# Router40_v2.net
KiCad netlist of a schematic drawn in EAGLE
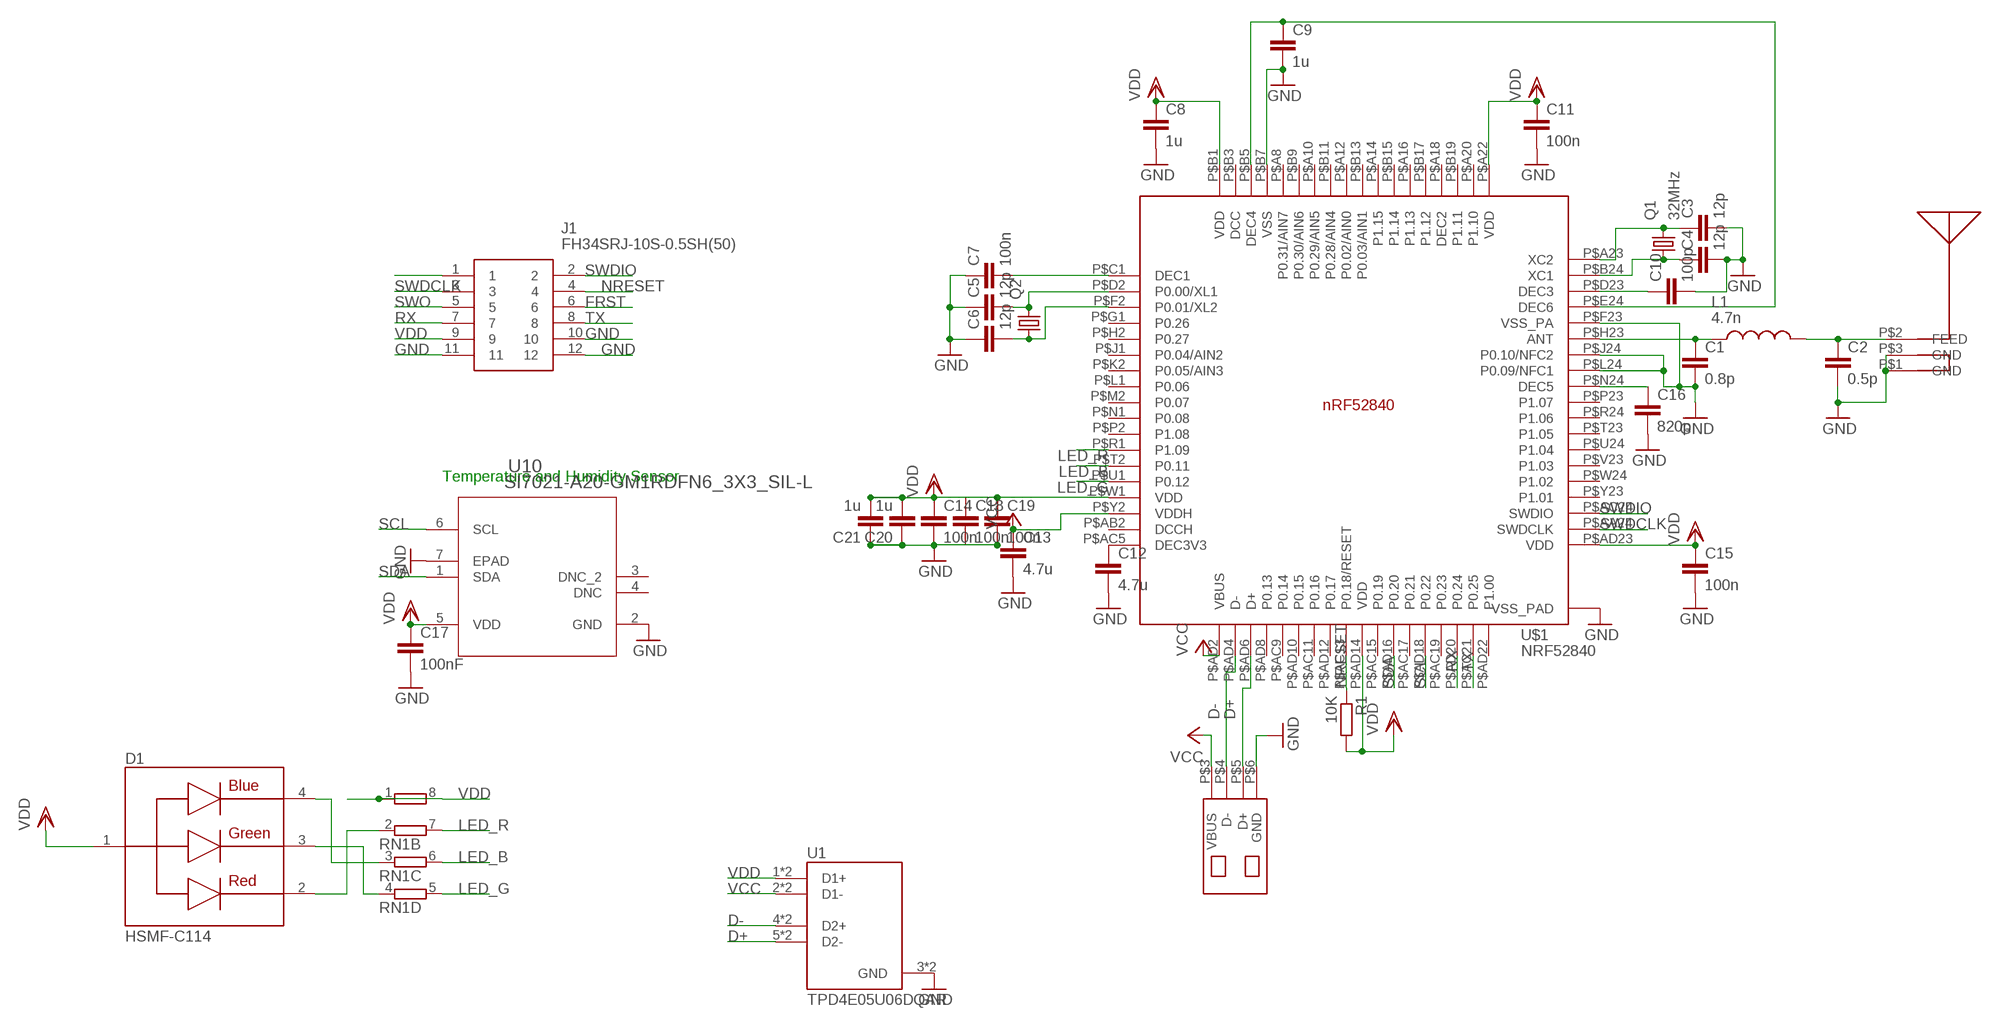
[diagram p0: schematic, sheet 1]

(export (version "E")
  (design (tool "Eeschema 10.0.6"))
  (components
    (comp (ref "C1")
      (value "0.8p")
      (footprint "eagle-import:C0402")
      (libsource (lib "eagle-import") (part "CC0402"))
    )
    (comp (ref "C2")
      (value "0.5p")
      (footprint "eagle-import:C0402")
      (libsource (lib "eagle-import") (part "CC0402"))
    )
    (comp (ref "C3")
      (value "12p")
      (footprint "eagle-import:C0402")
      (libsource (lib "eagle-import") (part "CC0402"))
    )
    (comp (ref "C4")
      (value "12p")
      (footprint "eagle-import:C0402")
      (libsource (lib "eagle-import") (part "CC0402"))
    )
    (comp (ref "C5")
      (value "12p")
      (footprint "eagle-import:C0402")
      (libsource (lib "eagle-import") (part "CC0402"))
    )
    (comp (ref "C6")
      (value "12p")
      (footprint "eagle-import:C0402")
      (libsource (lib "eagle-import") (part "CC0402"))
    )
    (comp (ref "C7")
      (value "100n")
      (footprint "eagle-import:C0402")
      (libsource (lib "eagle-import") (part "CC0402"))
    )
    (comp (ref "C8")
      (value "1u")
      (footprint "eagle-import:C0402")
      (libsource (lib "eagle-import") (part "CC0402"))
    )
    (comp (ref "C9")
      (value "1u")
      (footprint "eagle-import:C0402")
      (libsource (lib "eagle-import") (part "CC0402"))
    )
    (comp (ref "C10")
      (value "100p")
      (footprint "eagle-import:C0402")
      (libsource (lib "eagle-import") (part "CC0402"))
    )
    (comp (ref "C11")
      (value "100n")
      (footprint "eagle-import:C0402")
      (libsource (lib "eagle-import") (part "CC0402"))
    )
    (comp (ref "C12")
      (value "4.7u")
      (footprint "eagle-import:C0402")
      (libsource (lib "eagle-import") (part "CC0402"))
    )
    (comp (ref "C13")
      (value "4.7u")
      (footprint "eagle-import:C0402")
      (libsource (lib "eagle-import") (part "CC0402"))
    )
    (comp (ref "C14")
      (value "100n")
      (footprint "eagle-import:C0402")
      (libsource (lib "eagle-import") (part "CC0402"))
    )
    (comp (ref "C15")
      (value "100n")
      (footprint "eagle-import:C0402")
      (libsource (lib "eagle-import") (part "CC0402"))
    )
    (comp (ref "C16")
      (value "820p")
      (footprint "eagle-import:C0402")
      (libsource (lib "eagle-import") (part "CC0402"))
    )
    (comp (ref "C17")
      (value "100nF")
      (footprint "eagle-import:C0402")
      (libsource (lib "eagle-import") (part "CC0402"))
    )
    (comp (ref "C18")
      (value "100n")
      (footprint "eagle-import:C0402")
      (libsource (lib "eagle-import") (part "CC0402"))
    )
    (comp (ref "C19")
      (value "100n")
      (footprint "eagle-import:C0402")
      (libsource (lib "eagle-import") (part "CC0402"))
    )
    (comp (ref "C20")
      (value "1u")
      (footprint "eagle-import:C0603R")
      (libsource (lib "eagle-import") (part "CC0603R"))
    )
    (comp (ref "C21")
      (value "1u")
      (footprint "eagle-import:C0603R")
      (libsource (lib "eagle-import") (part "CC0603R"))
    )
    (comp (ref "D1")
      (value "HSMF-C114")
      (footprint "eagle-import:DIOSC160X150X35-4N")
      (fields (field (name "MF") "Broadcom Limited"))
      (libsource (lib "eagle-import") (part "HSMF-C114"))
    )
    (comp (ref "J1")
      (value "FH34SRJ-10S-0.5SH(50)")
      (footprint "eagle-import:FH34SRJ10S05SH50")
      (fields (field (name "MF") "Hirose Connector"))
      (libsource (lib "eagle-import") (part "FH34SRJ-10S-0.5SH(50)"))
    )
    (comp (ref "L1")
      (value "4.7n")
      (footprint "eagle-import:INDC0402X26N")
      (fields (field (name "MF") "TDK") (field (name "MP") "MHQ0402P7N5JT000"))
      (libsource (lib "eagle-import") (part "MHQ0402P7N5JT000"))
    )
    (comp (ref "Q1")
      (value "32MHz")
      (footprint "eagle-import:2.0X1.6_KX-5")
      (libsource (lib "eagle-import") (part "KX-5"))
    )
    (comp (ref "Q2")
      (value "KX-327-RT")
      (footprint "eagle-import:2.0X1.2")
      (libsource (lib "eagle-import") (part "KX-327-RT"))
    )
    (comp (ref "R1")
      (value "10K")
      (footprint "eagle-import:R0402")
      (libsource (lib "eagle-import") (part "RR0402"))
    )
    (comp (ref "RN1")
      (value "4R-N0402ARV341")
      (footprint "eagle-import:4X0402ARV341")
      (libsource (lib "eagle-import") (part "4R-N0402ARV341"))
    )
    (comp (ref "U$1")
      (value "NRF52840")
      (footprint "eagle-import:AQFN50P700X700X85_HS-74N")
      (libsource (lib "eagle-import") (part "NRF52840"))
    )
    (comp (ref "U$2")
      (value "USBA_MALE")
      (footprint "eagle-import:USBA_MALE")
      (libsource (lib "eagle-import") (part "USBA_MALE"))
    )
    (comp (ref "U$4")
      (value "CHIPANTENNAL2")
      (footprint "eagle-import:CHIPANTENNAL2")
      (libsource (lib "eagle-import") (part "CHIPANTENNAL2"))
    )
    (comp (ref "U1")
      (value "TPD4E05U06DQAR")
      (footprint "eagle-import:TI_TPD4E05U06DQAR")
      (fields (field (name "MF") "Texas Instruments"))
      (libsource (lib "eagle-import") (part "TPD4E05U06DQAR"))
    )
    (comp (ref "U10")
      (value "SI7021-A20-GM1RDFN6_3X3_SIL-L")
      (footprint "eagle-import:DFN6_3X3_SIL-L")
      (fields
        (field (name "MANUFACTURER_PART_NUMBER") "SI7021-A20-GM1R")
        (field (name "COPYRIGHT") "Copyright (C) 2018 Accelerated Designs. All rights reserved")
      )
      (libsource (lib "eagle-import") (part "SI7021-A20-GM1RDFN6_3X3_SIL-L"))
    )
  )
  (nets
    (net (code "1") (name "/D+") (class "Default")
      (node (ref "U$1") (pin "P$AD6") (pinfunction "D+_P$AD6") (pintype "bidirectional"))
      (node (ref "U$2") (pin "P$5") (pinfunction "D+_P$5") (pintype "bidirectional"))
      (node (ref "U1") (pin "5") (pinfunction "D2-_5") (pintype "bidirectional"))
      (node (ref "U1") (pin "6") (pinfunction "D2-_6") (pintype "bidirectional"))
    )
    (net (code "2") (name "/D-") (class "Default")
      (node (ref "U$1") (pin "P$AD4") (pinfunction "D-_P$AD4") (pintype "bidirectional"))
      (node (ref "U$2") (pin "P$4") (pinfunction "D-_P$4") (pintype "bidirectional"))
      (node (ref "U1") (pin "4") (pinfunction "D2+_4") (pintype "bidirectional"))
      (node (ref "U1") (pin "7") (pinfunction "D2+_7") (pintype "bidirectional"))
    )
    (net (code "3") (name "/FRST") (class "Default")
      (node (ref "J1") (pin "6") (pinfunction "6_6") (pintype "bidirectional"))
    )
    (net (code "4") (name "/LED_B") (class "Default")
      (node (ref "RN1") (pin "6") (pinfunction "2_6") (pintype "passive"))
      (node (ref "U$1") (pin "P$T2") (pinfunction "P0.11_P$T2") (pintype "bidirectional"))
    )
    (net (code "5") (name "/LED_G") (class "Default")
      (node (ref "RN1") (pin "5") (pinfunction "2_5") (pintype "passive"))
      (node (ref "U$1") (pin "P$U1") (pinfunction "P0.12_P$U1") (pintype "bidirectional"))
    )
    (net (code "6") (name "/LED_R") (class "Default")
      (node (ref "RN1") (pin "7") (pinfunction "2_7") (pintype "passive"))
      (node (ref "U$1") (pin "P$R1") (pinfunction "P1.09_P$R1") (pintype "bidirectional"))
    )
    (net (code "7") (name "/NRESET") (class "Default")
      (node (ref "J1") (pin "4") (pinfunction "4_4") (pintype "bidirectional"))
      (node (ref "R1") (pin "1") (pinfunction "1_1") (pintype "passive"))
      (node (ref "U$1") (pin "P$AC13") (pinfunction "P0.18/RESET_P$AC13") (pintype "bidirectional"))
    )
    (net (code "8") (name "/RX") (class "Default")
      (node (ref "J1") (pin "7") (pinfunction "7_7") (pintype "bidirectional"))
      (node (ref "U$1") (pin "P$AD20") (pinfunction "P0.24_P$AD20") (pintype "bidirectional"))
    )
    (net (code "9") (name "/SCL") (class "Default")
      (node (ref "U$1") (pin "P$AD18") (pinfunction "P0.22_P$AD18") (pintype "bidirectional"))
      (node (ref "U10") (pin "6") (pinfunction "SCL_6") (pintype "input"))
    )
    (net (code "10") (name "/SDA") (class "Default")
      (node (ref "U$1") (pin "P$AD16") (pinfunction "P0.20_P$AD16") (pintype "bidirectional"))
      (node (ref "U10") (pin "1") (pinfunction "SDA_1") (pintype "bidirectional"))
    )
    (net (code "11") (name "/SWDCLK") (class "Default")
      (node (ref "J1") (pin "3") (pinfunction "3_3") (pintype "bidirectional"))
      (node (ref "U$1") (pin "P$AA24") (pinfunction "SWDCLK_P$AA24") (pintype "input"))
    )
    (net (code "12") (name "/SWDIO") (class "Default")
      (node (ref "J1") (pin "2") (pinfunction "2_2") (pintype "bidirectional"))
      (node (ref "U$1") (pin "P$AC24") (pinfunction "SWDIO_P$AC24") (pintype "bidirectional"))
    )
    (net (code "13") (name "/SWO") (class "Default")
      (node (ref "J1") (pin "5") (pinfunction "5_5") (pintype "bidirectional"))
    )
    (net (code "14") (name "/TX") (class "Default")
      (node (ref "J1") (pin "8") (pinfunction "8_8") (pintype "bidirectional"))
      (node (ref "U$1") (pin "P$AC21") (pinfunction "P0.25_P$AC21") (pintype "bidirectional"))
    )
    (net (code "15") (name "GND") (class "Default")
      (node (ref "C1") (pin "2") (pinfunction "2_2") (pintype "passive"))
      (node (ref "C10") (pin "2") (pinfunction "2_2") (pintype "passive"))
      (node (ref "C11") (pin "2") (pinfunction "2_2") (pintype "passive"))
      (node (ref "C12") (pin "2") (pinfunction "2_2") (pintype "passive"))
      (node (ref "C13") (pin "2") (pinfunction "2_2") (pintype "passive"))
      (node (ref "C14") (pin "2") (pinfunction "2_2") (pintype "passive"))
      (node (ref "C15") (pin "2") (pinfunction "2_2") (pintype "passive"))
      (node (ref "C16") (pin "2") (pinfunction "2_2") (pintype "passive"))
      (node (ref "C17") (pin "2") (pinfunction "2_2") (pintype "passive"))
      (node (ref "C18") (pin "2") (pinfunction "2_2") (pintype "passive"))
      (node (ref "C19") (pin "2") (pinfunction "2_2") (pintype "passive"))
      (node (ref "C2") (pin "2") (pinfunction "2_2") (pintype "passive"))
      (node (ref "C20") (pin "1") (pinfunction "1_1") (pintype "passive"))
      (node (ref "C21") (pin "1") (pinfunction "1_1") (pintype "passive"))
      (node (ref "C3") (pin "2") (pinfunction "2_2") (pintype "passive"))
      (node (ref "C4") (pin "2") (pinfunction "2_2") (pintype "passive"))
      (node (ref "C5") (pin "1") (pinfunction "1_1") (pintype "passive"))
      (node (ref "C6") (pin "1") (pinfunction "1_1") (pintype "passive"))
      (node (ref "C7") (pin "1") (pinfunction "1_1") (pintype "passive"))
      (node (ref "C8") (pin "2") (pinfunction "2_2") (pintype "passive"))
      (node (ref "C9") (pin "2") (pinfunction "2_2") (pintype "passive"))
      (node (ref "J1") (pin "10") (pinfunction "10_10") (pintype "bidirectional"))
      (node (ref "J1") (pin "11") (pinfunction "11_11") (pintype "bidirectional"))
      (node (ref "J1") (pin "12") (pinfunction "12_12") (pintype "bidirectional"))
      (node (ref "U$1") (pin "P$74") (pinfunction "VSS_PAD_P$74") (pintype "bidirectional"))
      (node (ref "U$1") (pin "P$75") (pinfunction "VSS_PAD_P$75") (pintype "bidirectional"))
      (node (ref "U$1") (pin "P$76") (pinfunction "VSS_PAD_P$76") (pintype "bidirectional"))
      (node (ref "U$1") (pin "P$77") (pinfunction "VSS_PAD_P$77") (pintype "bidirectional"))
      (node (ref "U$1") (pin "P$78") (pinfunction "VSS_PAD_P$78") (pintype "bidirectional"))
      (node (ref "U$1") (pin "P$79") (pinfunction "VSS_PAD_P$79") (pintype "bidirectional"))
      (node (ref "U$1") (pin "P$80") (pinfunction "VSS_PAD_P$80") (pintype "bidirectional"))
      (node (ref "U$1") (pin "P$81") (pinfunction "VSS_PAD_P$81") (pintype "bidirectional"))
      (node (ref "U$1") (pin "P$82") (pinfunction "VSS_PAD_P$82") (pintype "bidirectional"))
      (node (ref "U$1") (pin "P$83") (pinfunction "VSS_PAD_P$83") (pintype "bidirectional"))
      (node (ref "U$1") (pin "P$84") (pinfunction "VSS_PAD_P$84") (pintype "bidirectional"))
      (node (ref "U$1") (pin "P$85") (pinfunction "VSS_PAD_P$85") (pintype "bidirectional"))
      (node (ref "U$1") (pin "P$86") (pinfunction "VSS_PAD_P$86") (pintype "bidirectional"))
      (node (ref "U$1") (pin "P$87") (pinfunction "VSS_PAD_P$87") (pintype "bidirectional"))
      (node (ref "U$1") (pin "P$88") (pinfunction "VSS_PAD_P$88") (pintype "bidirectional"))
      (node (ref "U$1") (pin "P$89") (pinfunction "VSS_PAD_P$89") (pintype "bidirectional"))
      (node (ref "U$1") (pin "P$90") (pinfunction "VSS_PAD_P$90") (pintype "bidirectional"))
      (node (ref "U$1") (pin "P$B7") (pinfunction "VSS_P$B7") (pintype "power_in"))
      (node (ref "U$1") (pin "P$F23") (pinfunction "VSS_PA_P$F23") (pintype "bidirectional"))
      (node (ref "U$1") (pin "P$J24") (pinfunction "P0.10/NFC2_P$J24") (pintype "bidirectional"))
      (node (ref "U$1") (pin "P$L24") (pinfunction "P0.09/NFC1_P$L24") (pintype "bidirectional"))
      (node (ref "U$2") (pin "P$6") (pinfunction "GND_P$6") (pintype "bidirectional"))
      (node (ref "U$4") (pin "P$1") (pinfunction "GND_P$1") (pintype "bidirectional"))
      (node (ref "U$4") (pin "P$3") (pinfunction "GND_P$3") (pintype "bidirectional"))
      (node (ref "U1") (pin "3") (pinfunction "GND_3") (pintype "power_in"))
      (node (ref "U1") (pin "8") (pinfunction "GND_8") (pintype "power_in"))
      (node (ref "U10") (pin "2") (pinfunction "GND_2") (pintype "power_in"))
      (node (ref "U10") (pin "7") (pinfunction "EPAD_7") (pintype "passive"))
    )
    (net (code "16") (name "Net-(Q1-2)") (class "Default")
      (node (ref "C3") (pin "1") (pinfunction "1_1") (pintype "passive"))
      (node (ref "Q1") (pin "3") (pinfunction "2_3") (pintype "passive"))
      (node (ref "U$1") (pin "P$A23") (pinfunction "XC2_P$A23") (pintype "output"))
    )
    (net (code "17") (name "Net-(RN1B-1)") (class "Default")
      (node (ref "D1") (pin "2") (pinfunction "2_2") (pintype "passive"))
      (node (ref "RN1") (pin "2") (pinfunction "1_2") (pintype "passive"))
    )
    (net (code "18") (name "Net-(RN1C-1)") (class "Default")
      (node (ref "D1") (pin "4") (pinfunction "4_4") (pintype "passive"))
      (node (ref "RN1") (pin "3") (pinfunction "1_3") (pintype "passive"))
    )
    (net (code "19") (name "Net-(RN1D-1)") (class "Default")
      (node (ref "D1") (pin "3") (pinfunction "3_3") (pintype "passive"))
      (node (ref "RN1") (pin "4") (pinfunction "1_4") (pintype "passive"))
    )
    (net (code "20") (name "Net-(U$1-ANT)") (class "Default")
      (node (ref "C1") (pin "1") (pinfunction "1_1") (pintype "passive"))
      (node (ref "L1") (pin "1") (pinfunction "1_1") (pintype "passive"))
      (node (ref "U$1") (pin "P$H23") (pinfunction "ANT_P$H23") (pintype "bidirectional"))
    )
    (net (code "21") (name "Net-(U$1-DEC1)") (class "Default")
      (node (ref "C7") (pin "2") (pinfunction "2_2") (pintype "passive"))
      (node (ref "U$1") (pin "P$C1") (pinfunction "DEC1_P$C1") (pintype "power_in"))
    )
    (net (code "22") (name "Net-(U$1-DEC3)") (class "Default")
      (node (ref "C10") (pin "1") (pinfunction "1_1") (pintype "passive"))
      (node (ref "U$1") (pin "P$D23") (pinfunction "DEC3_P$D23") (pintype "bidirectional"))
    )
    (net (code "23") (name "Net-(U$1-DEC3V3)") (class "Default")
      (node (ref "C12") (pin "1") (pinfunction "1_1") (pintype "passive"))
      (node (ref "U$1") (pin "P$AC5") (pinfunction "DEC3V3_P$AC5") (pintype "bidirectional"))
    )
    (net (code "24") (name "Net-(U$1-DEC4)") (class "Default")
      (node (ref "C9") (pin "1") (pinfunction "1_1") (pintype "passive"))
      (node (ref "U$1") (pin "P$B5") (pinfunction "DEC4_P$B5") (pintype "power_in"))
      (node (ref "U$1") (pin "P$E24") (pinfunction "DEC6_P$E24") (pintype "bidirectional"))
    )
    (net (code "25") (name "Net-(U$1-DEC5)") (class "Default")
      (node (ref "C16") (pin "1") (pinfunction "1_1") (pintype "passive"))
      (node (ref "U$1") (pin "P$N24") (pinfunction "DEC5_P$N24") (pintype "bidirectional"))
    )
    (net (code "26") (name "Net-(U$1-P0.00{slash}XL1)") (class "Default")
      (node (ref "C5") (pin "2") (pinfunction "2_2") (pintype "passive"))
      (node (ref "Q2") (pin "2") (pinfunction "2_2") (pintype "passive"))
      (node (ref "U$1") (pin "P$D2") (pinfunction "P0.00/XL1_P$D2") (pintype "bidirectional"))
    )
    (net (code "27") (name "Net-(U$1-P0.01{slash}XL2)") (class "Default")
      (node (ref "C6") (pin "2") (pinfunction "2_2") (pintype "passive"))
      (node (ref "Q2") (pin "1") (pinfunction "1_1") (pintype "passive"))
      (node (ref "U$1") (pin "P$F2") (pinfunction "P0.01/XL2_P$F2") (pintype "bidirectional"))
    )
    (net (code "28") (name "Net-(U$1-XC1)") (class "Default")
      (node (ref "C4") (pin "1") (pinfunction "1_1") (pintype "passive"))
      (node (ref "Q1") (pin "1") (pinfunction "1_1") (pintype "passive"))
      (node (ref "U$1") (pin "P$B24") (pinfunction "XC1_P$B24") (pintype "input"))
    )
    (net (code "29") (name "Net-(U$4-FEED)") (class "Default")
      (node (ref "C2") (pin "1") (pinfunction "1_1") (pintype "passive"))
      (node (ref "L1") (pin "2") (pinfunction "2_2") (pintype "passive"))
      (node (ref "U$4") (pin "P$2") (pinfunction "FEED_P$2") (pintype "bidirectional"))
    )
    (net (code "30") (name "VCC") (class "Default")
      (node (ref "C13") (pin "1") (pinfunction "1_1") (pintype "passive"))
      (node (ref "U$1") (pin "P$AD2") (pinfunction "VBUS_P$AD2") (pintype "power_in"))
      (node (ref "U$1") (pin "P$Y2") (pinfunction "VDDH_P$Y2") (pintype "power_in"))
      (node (ref "U$2") (pin "P$3") (pinfunction "VBUS_P$3") (pintype "bidirectional"))
      (node (ref "U1") (pin "2") (pinfunction "D1-_2") (pintype "bidirectional"))
      (node (ref "U1") (pin "9") (pinfunction "D1-_9") (pintype "bidirectional"))
    )
    (net (code "31") (name "VDD") (class "Default")
      (node (ref "C11") (pin "1") (pinfunction "1_1") (pintype "passive"))
      (node (ref "C14") (pin "1") (pinfunction "1_1") (pintype "passive"))
      (node (ref "C15") (pin "1") (pinfunction "1_1") (pintype "passive"))
      (node (ref "C17") (pin "1") (pinfunction "1_1") (pintype "passive"))
      (node (ref "C18") (pin "1") (pinfunction "1_1") (pintype "passive"))
      (node (ref "C19") (pin "1") (pinfunction "1_1") (pintype "passive"))
      (node (ref "C20") (pin "2") (pinfunction "2_2") (pintype "passive"))
      (node (ref "C21") (pin "2") (pinfunction "2_2") (pintype "passive"))
      (node (ref "C8") (pin "1") (pinfunction "1_1") (pintype "passive"))
      (node (ref "D1") (pin "1") (pinfunction "1_1") (pintype "passive"))
      (node (ref "J1") (pin "9") (pinfunction "9_9") (pintype "bidirectional"))
      (node (ref "R1") (pin "2") (pinfunction "2_2") (pintype "passive"))
      (node (ref "RN1") (pin "1") (pinfunction "1_1") (pintype "passive"))
      (node (ref "RN1") (pin "8") (pinfunction "2_8") (pintype "passive"))
      (node (ref "U$1") (pin "P$A22") (pinfunction "VDD_P$A22") (pintype "power_in"))
      (node (ref "U$1") (pin "P$AD14") (pinfunction "VDD_P$AD14") (pintype "power_in"))
      (node (ref "U$1") (pin "P$AD23") (pinfunction "VDD_P$AD23") (pintype "power_in"))
      (node (ref "U$1") (pin "P$B1") (pinfunction "VDD_P$B1") (pintype "power_in"))
      (node (ref "U$1") (pin "P$W1") (pinfunction "VDD_P$W1") (pintype "power_in"))
      (node (ref "U1") (pin "1") (pinfunction "D1+_1") (pintype "bidirectional"))
      (node (ref "U1") (pin "10") (pinfunction "D1+_10") (pintype "bidirectional"))
      (node (ref "U10") (pin "5") (pinfunction "VDD_5") (pintype "power_in"))
    )
    (net (code "32") (name "unconnected-(J1-Pad1)") (class "Default")
      (node (ref "J1") (pin "1") (pinfunction "1_1") (pintype "bidirectional"))
    )
    (net (code "33") (name "unconnected-(U$1-DCC-PadP$B3)") (class "Default")
      (node (ref "U$1") (pin "P$B3") (pinfunction "DCC_P$B3") (pintype "output"))
    )
    (net (code "34") (name "unconnected-(U$1-DCCH-PadP$AB2)") (class "Default")
      (node (ref "U$1") (pin "P$AB2") (pinfunction "DCCH_P$AB2") (pintype "bidirectional"))
    )
    (net (code "35") (name "unconnected-(U$1-DEC2-PadP$A18)") (class "Default")
      (node (ref "U$1") (pin "P$A18") (pinfunction "DEC2_P$A18") (pintype "bidirectional"))
    )
    (net (code "36") (name "unconnected-(U$1-P0.02{slash}AIN0-PadP$A12)") (class "Default")
      (node (ref "U$1") (pin "P$A12") (pinfunction "P0.02/AIN0_P$A12") (pintype "bidirectional"))
    )
    (net (code "37") (name "unconnected-(U$1-P0.03{slash}AIN1-PadP$B13)") (class "Default")
      (node (ref "U$1") (pin "P$B13") (pinfunction "P0.03/AIN1_P$B13") (pintype "bidirectional"))
    )
    (net (code "38") (name "unconnected-(U$1-P0.04{slash}AIN2-PadP$J1)") (class "Default")
      (node (ref "U$1") (pin "P$J1") (pinfunction "P0.04/AIN2_P$J1") (pintype "bidirectional"))
    )
    (net (code "39") (name "unconnected-(U$1-P0.05{slash}AIN3-PadP$K2)") (class "Default")
      (node (ref "U$1") (pin "P$K2") (pinfunction "P0.05/AIN3_P$K2") (pintype "bidirectional"))
    )
    (net (code "40") (name "unconnected-(U$1-P0.06-PadP$L1)") (class "Default")
      (node (ref "U$1") (pin "P$L1") (pinfunction "P0.06_P$L1") (pintype "bidirectional"))
    )
    (net (code "41") (name "unconnected-(U$1-P0.07-PadP$M2)") (class "Default")
      (node (ref "U$1") (pin "P$M2") (pinfunction "P0.07_P$M2") (pintype "bidirectional"))
    )
    (net (code "42") (name "unconnected-(U$1-P0.08-PadP$N1)") (class "Default")
      (node (ref "U$1") (pin "P$N1") (pinfunction "P0.08_P$N1") (pintype "bidirectional"))
    )
    (net (code "43") (name "unconnected-(U$1-P0.13-PadP$AD8)") (class "Default")
      (node (ref "U$1") (pin "P$AD8") (pinfunction "P0.13_P$AD8") (pintype "bidirectional"))
    )
    (net (code "44") (name "unconnected-(U$1-P0.14-PadP$AC9)") (class "Default")
      (node (ref "U$1") (pin "P$AC9") (pinfunction "P0.14_P$AC9") (pintype "bidirectional"))
    )
    (net (code "45") (name "unconnected-(U$1-P0.15-PadP$AD10)") (class "Default")
      (node (ref "U$1") (pin "P$AD10") (pinfunction "P0.15_P$AD10") (pintype "bidirectional"))
    )
    (net (code "46") (name "unconnected-(U$1-P0.16-PadP$AC11)") (class "Default")
      (node (ref "U$1") (pin "P$AC11") (pinfunction "P0.16_P$AC11") (pintype "bidirectional"))
    )
    (net (code "47") (name "unconnected-(U$1-P0.17-PadP$AD12)") (class "Default")
      (node (ref "U$1") (pin "P$AD12") (pinfunction "P0.17_P$AD12") (pintype "bidirectional"))
    )
    (net (code "48") (name "unconnected-(U$1-P0.19-PadP$AC15)") (class "Default")
      (node (ref "U$1") (pin "P$AC15") (pinfunction "P0.19_P$AC15") (pintype "bidirectional"))
    )
    (net (code "49") (name "unconnected-(U$1-P0.21-PadP$AC17)") (class "Default")
      (node (ref "U$1") (pin "P$AC17") (pinfunction "P0.21_P$AC17") (pintype "bidirectional"))
    )
    (net (code "50") (name "unconnected-(U$1-P0.23-PadP$AC19)") (class "Default")
      (node (ref "U$1") (pin "P$AC19") (pinfunction "P0.23_P$AC19") (pintype "bidirectional"))
    )
    (net (code "51") (name "unconnected-(U$1-P0.26-PadP$G1)") (class "Default")
      (node (ref "U$1") (pin "P$G1") (pinfunction "P0.26_P$G1") (pintype "bidirectional"))
    )
    (net (code "52") (name "unconnected-(U$1-P0.27-PadP$H2)") (class "Default")
      (node (ref "U$1") (pin "P$H2") (pinfunction "P0.27_P$H2") (pintype "bidirectional"))
    )
    (net (code "53") (name "unconnected-(U$1-P0.28{slash}AIN4-PadP$B11)") (class "Default")
      (node (ref "U$1") (pin "P$B11") (pinfunction "P0.28/AIN4_P$B11") (pintype "bidirectional"))
    )
    (net (code "54") (name "unconnected-(U$1-P0.29{slash}AIN5-PadP$A10)") (class "Default")
      (node (ref "U$1") (pin "P$A10") (pinfunction "P0.29/AIN5_P$A10") (pintype "bidirectional"))
    )
    (net (code "55") (name "unconnected-(U$1-P0.30{slash}AIN6-PadP$B9)") (class "Default")
      (node (ref "U$1") (pin "P$B9") (pinfunction "P0.30/AIN6_P$B9") (pintype "bidirectional"))
    )
    (net (code "56") (name "unconnected-(U$1-P0.31{slash}AIN7-PadP$A8)") (class "Default")
      (node (ref "U$1") (pin "P$A8") (pinfunction "P0.31/AIN7_P$A8") (pintype "bidirectional"))
    )
    (net (code "57") (name "unconnected-(U$1-P1.00-PadP$AD22)") (class "Default")
      (node (ref "U$1") (pin "P$AD22") (pinfunction "P1.00_P$AD22") (pintype "bidirectional"))
    )
    (net (code "58") (name "unconnected-(U$1-P1.01-PadP$Y23)") (class "Default")
      (node (ref "U$1") (pin "P$Y23") (pinfunction "P1.01_P$Y23") (pintype "bidirectional"))
    )
    (net (code "59") (name "unconnected-(U$1-P1.02-PadP$W24)") (class "Default")
      (node (ref "U$1") (pin "P$W24") (pinfunction "P1.02_P$W24") (pintype "bidirectional"))
    )
    (net (code "60") (name "unconnected-(U$1-P1.03-PadP$V23)") (class "Default")
      (node (ref "U$1") (pin "P$V23") (pinfunction "P1.03_P$V23") (pintype "bidirectional"))
    )
    (net (code "61") (name "unconnected-(U$1-P1.04-PadP$U24)") (class "Default")
      (node (ref "U$1") (pin "P$U24") (pinfunction "P1.04_P$U24") (pintype "bidirectional"))
    )
    (net (code "62") (name "unconnected-(U$1-P1.05-PadP$T23)") (class "Default")
      (node (ref "U$1") (pin "P$T23") (pinfunction "P1.05_P$T23") (pintype "bidirectional"))
    )
    (net (code "63") (name "unconnected-(U$1-P1.06-PadP$R24)") (class "Default")
      (node (ref "U$1") (pin "P$R24") (pinfunction "P1.06_P$R24") (pintype "bidirectional"))
    )
    (net (code "64") (name "unconnected-(U$1-P1.07-PadP$P23)") (class "Default")
      (node (ref "U$1") (pin "P$P23") (pinfunction "P1.07_P$P23") (pintype "bidirectional"))
    )
    (net (code "65") (name "unconnected-(U$1-P1.08-PadP$P2)") (class "Default")
      (node (ref "U$1") (pin "P$P2") (pinfunction "P1.08_P$P2") (pintype "bidirectional"))
    )
    (net (code "66") (name "unconnected-(U$1-P1.10-PadP$A20)") (class "Default")
      (node (ref "U$1") (pin "P$A20") (pinfunction "P1.10_P$A20") (pintype "bidirectional"))
    )
    (net (code "67") (name "unconnected-(U$1-P1.11-PadP$B19)") (class "Default")
      (node (ref "U$1") (pin "P$B19") (pinfunction "P1.11_P$B19") (pintype "bidirectional"))
    )
    (net (code "68") (name "unconnected-(U$1-P1.12-PadP$B17)") (class "Default")
      (node (ref "U$1") (pin "P$B17") (pinfunction "P1.12_P$B17") (pintype "bidirectional"))
    )
    (net (code "69") (name "unconnected-(U$1-P1.13-PadP$A16)") (class "Default")
      (node (ref "U$1") (pin "P$A16") (pinfunction "P1.13_P$A16") (pintype "bidirectional"))
    )
    (net (code "70") (name "unconnected-(U$1-P1.14-PadP$B15)") (class "Default")
      (node (ref "U$1") (pin "P$B15") (pinfunction "P1.14_P$B15") (pintype "bidirectional"))
    )
    (net (code "71") (name "unconnected-(U$1-P1.15-PadP$A14)") (class "Default")
      (node (ref "U$1") (pin "P$A14") (pinfunction "P1.15_P$A14") (pintype "bidirectional"))
    )
    (net (code "72") (name "unconnected-(U10-DNC-Pad4)") (class "Default")
      (node (ref "U10") (pin "4") (pinfunction "DNC_4") (pintype "no_connect"))
    )
    (net (code "73") (name "unconnected-(U10-DNC_2-Pad3)") (class "Default")
      (node (ref "U10") (pin "3") (pinfunction "DNC_2_3") (pintype "no_connect"))
    )
  )
)
